# Fet_Module.net
KiCad netlist of a schematic drawn in Altium Designer
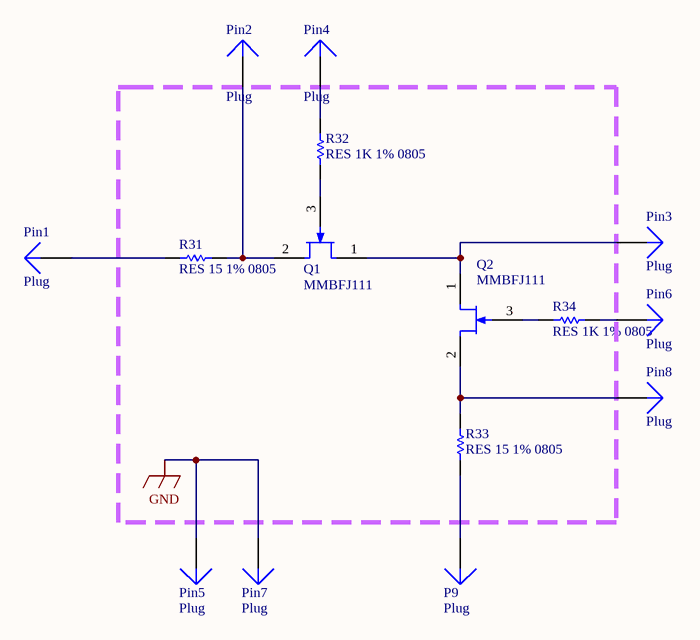
[diagram p0: Fet Module.SchDoc]

(export (version "E")
  (design (tool "Eeschema 10.0.6"))
  (components
    (comp (ref "P9")
      (value "Plug")
      (footprint "PIN1")
      (fields (field (name "PUBLISHER") "Altium Limited"))
      (libsource (lib "Miscellaneous Connectors") (part "Plug"))
    )
    (comp (ref "Pin1")
      (value "Plug")
      (footprint "PIN1")
      (fields (field (name "PUBLISHER") "Altium Limited"))
      (libsource (lib "Miscellaneous Connectors") (part "Plug"))
    )
    (comp (ref "Pin2")
      (value "Plug")
      (footprint "PIN1")
      (fields (field (name "PUBLISHER") "Altium Limited"))
      (libsource (lib "Miscellaneous Connectors") (part "Plug"))
    )
    (comp (ref "Pin3")
      (value "Plug")
      (footprint "PIN1")
      (fields (field (name "PUBLISHER") "Altium Limited"))
      (libsource (lib "Miscellaneous Connectors") (part "Plug"))
    )
    (comp (ref "Pin4")
      (value "Plug")
      (footprint "PIN1")
      (fields (field (name "PUBLISHER") "Altium Limited"))
      (libsource (lib "Miscellaneous Connectors") (part "Plug"))
    )
    (comp (ref "Pin5")
      (value "Plug")
      (footprint "PIN1")
      (fields (field (name "PUBLISHER") "Altium Limited"))
      (libsource (lib "Miscellaneous Connectors") (part "Plug"))
    )
    (comp (ref "Pin6")
      (value "Plug")
      (footprint "PIN1")
      (fields (field (name "PUBLISHER") "Altium Limited"))
      (libsource (lib "Miscellaneous Connectors") (part "Plug"))
    )
    (comp (ref "Pin7")
      (value "Plug")
      (footprint "PIN1")
      (fields (field (name "PUBLISHER") "Altium Limited"))
      (libsource (lib "Miscellaneous Connectors") (part "Plug"))
    )
    (comp (ref "Pin8")
      (value "Plug")
      (footprint "PIN1")
      (fields (field (name "PUBLISHER") "Altium Limited"))
      (libsource (lib "Miscellaneous Connectors") (part "Plug"))
    )
    (comp (ref "Q1")
      (value "MMBFJ111")
      (footprint "ONSC-SOT-23-3-318-08_V")
      (description "JFET - VHF / UJFET Chopper")
      (fields (field (name "PARTNUMBER") "MMBFJ310LT3") (field (name "MANUFACTURER") "On Semiconductor"))
      (libsource (lib "Altium Content Vault") (part "CMP-1062-00038-1"))
    )
    (comp (ref "Q2")
      (value "MMBFJ111")
      (footprint "ONSC-SOT-23-3-318-08_V")
      (description "JFET - VHF / UJFET Chopper")
      (fields (field (name "PARTNUMBER") "MMBFJ310LT3") (field (name "MANUFACTURER") "On Semiconductor"))
      (libsource (lib "Altium Content Vault") (part "CMP-1062-00038-1"))
    )
    (comp (ref "R31")
      (value "RES 15 1% 0805")
      (footprint "RESC2013X70X40LL20T20")
      (description "Resistor 15 1% 0805  0.2W 10ppm/C")
      (fields (field (name "MANUFACTURER") "Panasonic"))
      (libsource (lib "Altium Content Vault") (part "CMP-2001-00110-5"))
    )
    (comp (ref "R32")
      (value "RES 1K 1% 0805")
      (footprint "RESC2013X70X40LL20T20")
      (description "Resistor 1K 1% 0805  0.2W 10ppm/C")
      (fields (field (name "MANUFACTURER") "Panasonic"))
      (libsource (lib "Altium Content Vault") (part "CMP-2001-00110-5"))
    )
    (comp (ref "R33")
      (value "RES 15 1% 0805")
      (footprint "RESC2013X70X40LL20T20")
      (description "Resistor 15 1% 0805  0.2W 10ppm/C")
      (fields (field (name "MANUFACTURER") "Panasonic"))
      (libsource (lib "Altium Content Vault") (part "CMP-2001-00110-5"))
    )
    (comp (ref "R34")
      (value "RES 1K 1% 0805")
      (footprint "RESC2013X70X40LL20T20")
      (description "Resistor 1K1% 0805  0.2W 10ppm/C")
      (fields (field (name "MANUFACTURER") "Panasonic"))
      (libsource (lib "Altium Content Vault") (part "CMP-2001-00110-5"))
    )
  )
  (nets
    (net (code "1") (name "GND") (class "Default")
      (node (ref "Pin5") (pin "1") (pinfunction "1_1") (pintype "passive"))
      (node (ref "Pin7") (pin "1") (pinfunction "1_1") (pintype "passive"))
    )
    (net (code "2") (name "Net-(P9-Pad1)") (class "Default")
      (node (ref "P9") (pin "1") (pinfunction "1_1") (pintype "passive"))
      (node (ref "R33") (pin "2") (pinfunction "2_2") (pintype "passive"))
    )
    (net (code "3") (name "Net-(Pin1-Pad1)") (class "Default")
      (node (ref "Pin1") (pin "1") (pinfunction "1_1") (pintype "passive"))
      (node (ref "R31") (pin "2") (pinfunction "2_2") (pintype "passive"))
    )
    (net (code "4") (name "Net-(Pin4-Pad1)") (class "Default")
      (node (ref "Pin4") (pin "1") (pinfunction "1_1") (pintype "passive"))
      (node (ref "R32") (pin "1") (pinfunction "1_1") (pintype "passive"))
    )
    (net (code "5") (name "Net-(Pin6-Pad1)") (class "Default")
      (node (ref "Pin6") (pin "1") (pinfunction "1_1") (pintype "passive"))
      (node (ref "R34") (pin "2") (pinfunction "2_2") (pintype "passive"))
    )
    (net (code "6") (name "Net-(Q1-D)") (class "Default")
      (node (ref "Pin3") (pin "1") (pinfunction "1_1") (pintype "passive"))
      (node (ref "Q1") (pin "1") (pinfunction "D_1") (pintype "passive"))
      (node (ref "Q2") (pin "1") (pinfunction "D_1") (pintype "passive"))
    )
    (net (code "7") (name "Net-(Q1-G)") (class "Default")
      (node (ref "Q1") (pin "3") (pinfunction "G_3") (pintype "passive"))
      (node (ref "R32") (pin "2") (pinfunction "2_2") (pintype "passive"))
    )
    (net (code "8") (name "Net-(Q1-S)") (class "Default")
      (node (ref "Pin2") (pin "1") (pinfunction "1_1") (pintype "passive"))
      (node (ref "Q1") (pin "2") (pinfunction "S_2") (pintype "passive"))
      (node (ref "R31") (pin "1") (pinfunction "1_1") (pintype "passive"))
    )
    (net (code "9") (name "Net-(Q2-G)") (class "Default")
      (node (ref "Q2") (pin "3") (pinfunction "G_3") (pintype "passive"))
      (node (ref "R34") (pin "1") (pinfunction "1_1") (pintype "passive"))
    )
    (net (code "10") (name "Net-(Q2-S)") (class "Default")
      (node (ref "Pin8") (pin "1") (pinfunction "1_1") (pintype "passive"))
      (node (ref "Q2") (pin "2") (pinfunction "S_2") (pintype "passive"))
      (node (ref "R33") (pin "1") (pinfunction "1_1") (pintype "passive"))
    )
  )
)
